# FonteTens_o.net
KiCad netlist of a schematic drawn in Altium Designer
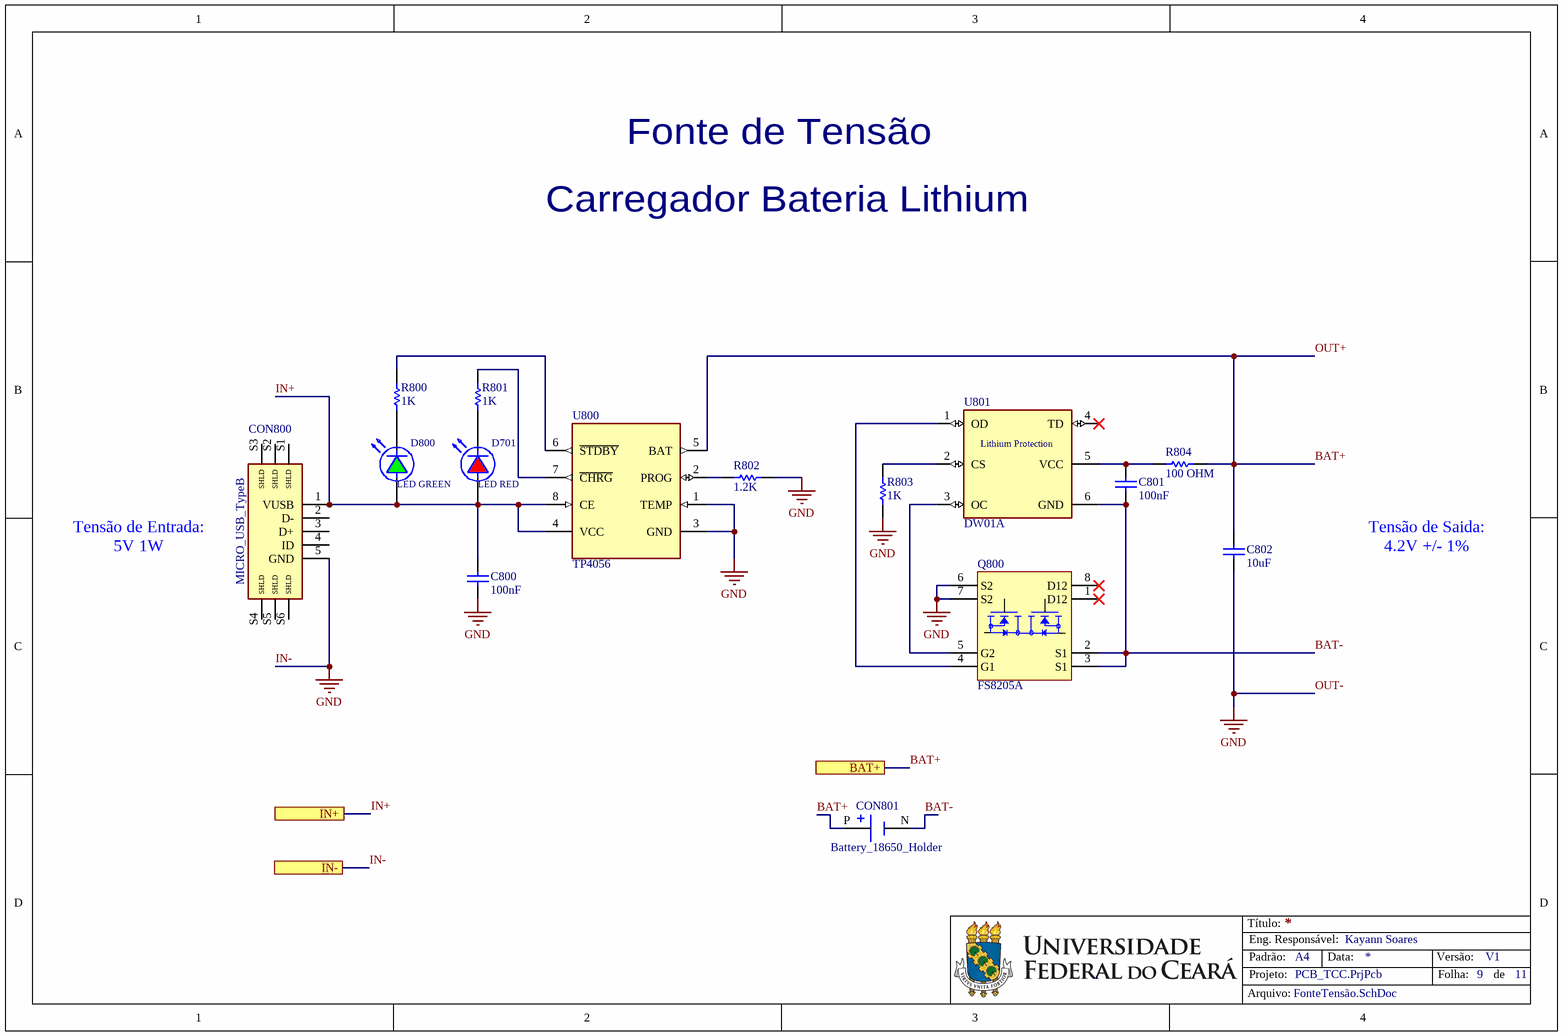
[diagram p0: FonteTensão.SchDoc]

(export (version "E")
  (design (tool "Eeschema 10.0.6"))
  (components
    (comp (ref "C800") (value "100nF") (libsource (lib "PCB_TCC") (part "CAP_CER_100nF_0603")))
    (comp (ref "C801") (value "100nF") (libsource (lib "PCB_TCC") (part "CAP_CER_100nF_0603")))
    (comp (ref "C802")
      (value "10uF")
      (footprint "CAP_CER_0805")
      (libsource (lib "PCB_TCC") (part "CAP_CER_10uF_0805"))
    )
    (comp (ref "CON800")
      (value "MICRO_USB_TypeB")
      (footprint "MICRO_USB_TypeB")
      (libsource (lib "PCB_TCC") (part "MICRO_USB_TypeB"))
    )
    (comp (ref "CON801")
      (value "Battery_18650_Holder")
      (footprint "Battery_18650_Holder")
      (libsource (lib "PCB_TCC") (part "Battery_18650_Holder"))
    )
    (comp (ref "D701")
      (value "LED RED")
      (footprint "LED_RED_SMD_0603")
      (libsource (lib "PCB_TCC") (part "LED_RED_SMD_0603"))
    )
    (comp (ref "D800")
      (value "LED GREEN")
      (footprint "LED_GREEN_SMD_0603")
      (libsource (lib "PCB_TCC") (part "LED_GREEN_SMD_0603"))
    )
    (comp (ref "Q800") (value "FS8205A") (footprint "FS8205A") (libsource (lib "PCB_TCC") (part "FS8205A")))
    (comp (ref "R800") (value "1K") (footprint "RES_0603") (libsource (lib "PCB_TCC") (part "RES_1K_0603")))
    (comp (ref "R801") (value "1K") (footprint "RES_0603") (libsource (lib "PCB_TCC") (part "RES_1K_0603")))
    (comp (ref "R802")
      (value "1.2K")
      (footprint "CAP_CER_0805")
      (libsource (lib "PCB_TCC") (part "RES_1.2K_0805"))
    )
    (comp (ref "R803") (value "1K") (footprint "RES_0603") (libsource (lib "PCB_TCC") (part "RES_1K_0603")))
    (comp (ref "R804")
      (value "100 OHM")
      (footprint "RES_0603")
      (libsource (lib "PCB_TCC") (part "RES_100OHM_0603"))
    )
    (comp (ref "U800") (value "TP4056") (footprint "TP4056") (libsource (lib "PCB_TCC") (part "TP4056")))
    (comp (ref "U801") (value "DW01A") (footprint "DW01A") (libsource (lib "PCB_TCC") (part "DW01A")))
  )
  (nets
    (net (code "1") (name "/BAT+") (class "Default")
      (node (ref "C802") (pin "2") (pinfunction "2_2") (pintype "passive"))
      (node (ref "CON801") (pin "P") (pinfunction "POS_P") (pintype "passive"))
      (node (ref "R804") (pin "2") (pinfunction "2_2") (pintype "passive"))
      (node (ref "U800") (pin "5") (pinfunction "BAT_5") (pintype "output"))
    )
    (net (code "2") (name "/BAT-") (class "Default")
      (node (ref "C801") (pin "1") (pinfunction "1_1") (pintype "passive"))
      (node (ref "CON801") (pin "N") (pinfunction "NEG_N") (pintype "passive"))
      (node (ref "Q800") (pin "2") (pinfunction "S1_2") (pintype "passive"))
      (node (ref "Q800") (pin "3") (pinfunction "S1_3") (pintype "passive"))
      (node (ref "U801") (pin "6") (pinfunction "GND_6") (pintype "power_in"))
    )
    (net (code "3") (name "/IN+") (class "Default")
      (node (ref "C800") (pin "2") (pinfunction "2_2") (pintype "passive"))
      (node (ref "CON800") (pin "1") (pinfunction "VUSB_1") (pintype "passive"))
      (node (ref "D701") (pin "A") (pinfunction "A_A") (pintype "passive"))
      (node (ref "D800") (pin "A") (pinfunction "A_A") (pintype "passive"))
      (node (ref "U800") (pin "4") (pinfunction "VCC_4") (pintype "power_in"))
      (node (ref "U800") (pin "8") (pinfunction "CE_8") (pintype "input"))
    )
    (net (code "4") (name "GND") (class "Default")
      (node (ref "C800") (pin "1") (pinfunction "1_1") (pintype "passive"))
      (node (ref "C802") (pin "1") (pinfunction "1_1") (pintype "passive"))
      (node (ref "CON800") (pin "5") (pinfunction "GND_5") (pintype "passive"))
      (node (ref "Q800") (pin "6") (pinfunction "S2_6") (pintype "passive"))
      (node (ref "Q800") (pin "7") (pinfunction "S2_7") (pintype "passive"))
      (node (ref "R802") (pin "2") (pinfunction "2_2") (pintype "passive"))
      (node (ref "R803") (pin "1") (pinfunction "1_1") (pintype "passive"))
      (node (ref "U800") (pin "1") (pinfunction "TEMP_1") (pintype "input"))
      (node (ref "U800") (pin "3") (pinfunction "GND_3") (pintype "power_in"))
    )
    (net (code "5") (name "Net-(D701-PadK)") (class "Default")
      (node (ref "D701") (pin "K") (pinfunction "K_K") (pintype "passive"))
      (node (ref "R801") (pin "1") (pinfunction "1_1") (pintype "passive"))
    )
    (net (code "6") (name "Net-(D800-PadK)") (class "Default")
      (node (ref "D800") (pin "K") (pinfunction "K_K") (pintype "passive"))
      (node (ref "R800") (pin "1") (pinfunction "1_1") (pintype "passive"))
    )
    (net (code "7") (name "Net-(Q800-G1)") (class "Default")
      (node (ref "Q800") (pin "4") (pinfunction "G1_4") (pintype "passive"))
      (node (ref "U801") (pin "1") (pinfunction "OD_1") (pintype "bidirectional"))
    )
    (net (code "8") (name "Net-(Q800-G2)") (class "Default")
      (node (ref "Q800") (pin "5") (pinfunction "G2_5") (pintype "passive"))
      (node (ref "U801") (pin "3") (pinfunction "OC_3") (pintype "bidirectional"))
    )
    (net (code "9") (name "Net-(U800-PROG)") (class "Default")
      (node (ref "R802") (pin "1") (pinfunction "1_1") (pintype "passive"))
      (node (ref "U800") (pin "2") (pinfunction "PROG_2") (pintype "bidirectional"))
    )
    (net (code "10") (name "Net-(U800-~{CHRG})") (class "Default")
      (node (ref "R801") (pin "2") (pinfunction "2_2") (pintype "passive"))
      (node (ref "U800") (pin "7") (pinfunction "~{CHRG}_7") (pintype "output"))
    )
    (net (code "11") (name "Net-(U800-~{STDBY})") (class "Default")
      (node (ref "R800") (pin "2") (pinfunction "2_2") (pintype "passive"))
      (node (ref "U800") (pin "6") (pinfunction "~{STDBY}_6") (pintype "output"))
    )
    (net (code "12") (name "Net-(U801-CS)") (class "Default")
      (node (ref "R803") (pin "2") (pinfunction "2_2") (pintype "passive"))
      (node (ref "U801") (pin "2") (pinfunction "CS_2") (pintype "bidirectional"))
    )
    (net (code "13") (name "Net-(U801-VCC)") (class "Default")
      (node (ref "C801") (pin "2") (pinfunction "2_2") (pintype "passive"))
      (node (ref "R804") (pin "1") (pinfunction "1_1") (pintype "passive"))
      (node (ref "U801") (pin "5") (pinfunction "VCC_5") (pintype "power_in"))
    )
    (net (code "14") (name "unconnected-(CON800-D+-Pad3)") (class "Default")
      (node (ref "CON800") (pin "3") (pinfunction "D+_3") (pintype "passive"))
    )
    (net (code "15") (name "unconnected-(CON800-D--Pad2)") (class "Default")
      (node (ref "CON800") (pin "2") (pinfunction "D-_2") (pintype "passive"))
    )
    (net (code "16") (name "unconnected-(CON800-ID-Pad4)") (class "Default")
      (node (ref "CON800") (pin "4") (pinfunction "ID_4") (pintype "passive"))
    )
    (net (code "17") (name "unconnected-(CON800-SHLD-PadS1)") (class "Default")
      (node (ref "CON800") (pin "S1") (pinfunction "SHLD_S1") (pintype "passive"))
    )
    (net (code "18") (name "unconnected-(CON800-SHLD-PadS2)") (class "Default")
      (node (ref "CON800") (pin "S2") (pinfunction "SHLD_S2") (pintype "passive"))
    )
    (net (code "19") (name "unconnected-(CON800-SHLD-PadS3)") (class "Default")
      (node (ref "CON800") (pin "S3") (pinfunction "SHLD_S3") (pintype "passive"))
    )
    (net (code "20") (name "unconnected-(CON800-SHLD-PadS4)") (class "Default")
      (node (ref "CON800") (pin "S4") (pinfunction "SHLD_S4") (pintype "passive"))
    )
    (net (code "21") (name "unconnected-(CON800-SHLD-PadS5)") (class "Default")
      (node (ref "CON800") (pin "S5") (pinfunction "SHLD_S5") (pintype "passive"))
    )
    (net (code "22") (name "unconnected-(CON800-SHLD-PadS6)") (class "Default")
      (node (ref "CON800") (pin "S6") (pinfunction "SHLD_S6") (pintype "passive"))
    )
    (net (code "23") (name "unconnected-(Q800-D12-Pad1)") (class "Default")
      (node (ref "Q800") (pin "1") (pinfunction "D12_1") (pintype "passive+no_connect"))
    )
    (net (code "24") (name "unconnected-(Q800-D12-Pad8)") (class "Default")
      (node (ref "Q800") (pin "8") (pinfunction "D12_8") (pintype "passive+no_connect"))
    )
    (net (code "25") (name "unconnected-(U801-TD-Pad4)") (class "Default")
      (node (ref "U801") (pin "4") (pinfunction "TD_4") (pintype "bidirectional+no_connect"))
    )
  )
)
